# ArbPwrBoost_P3.net
KiCad netlist of a schematic drawn in Altium Designer
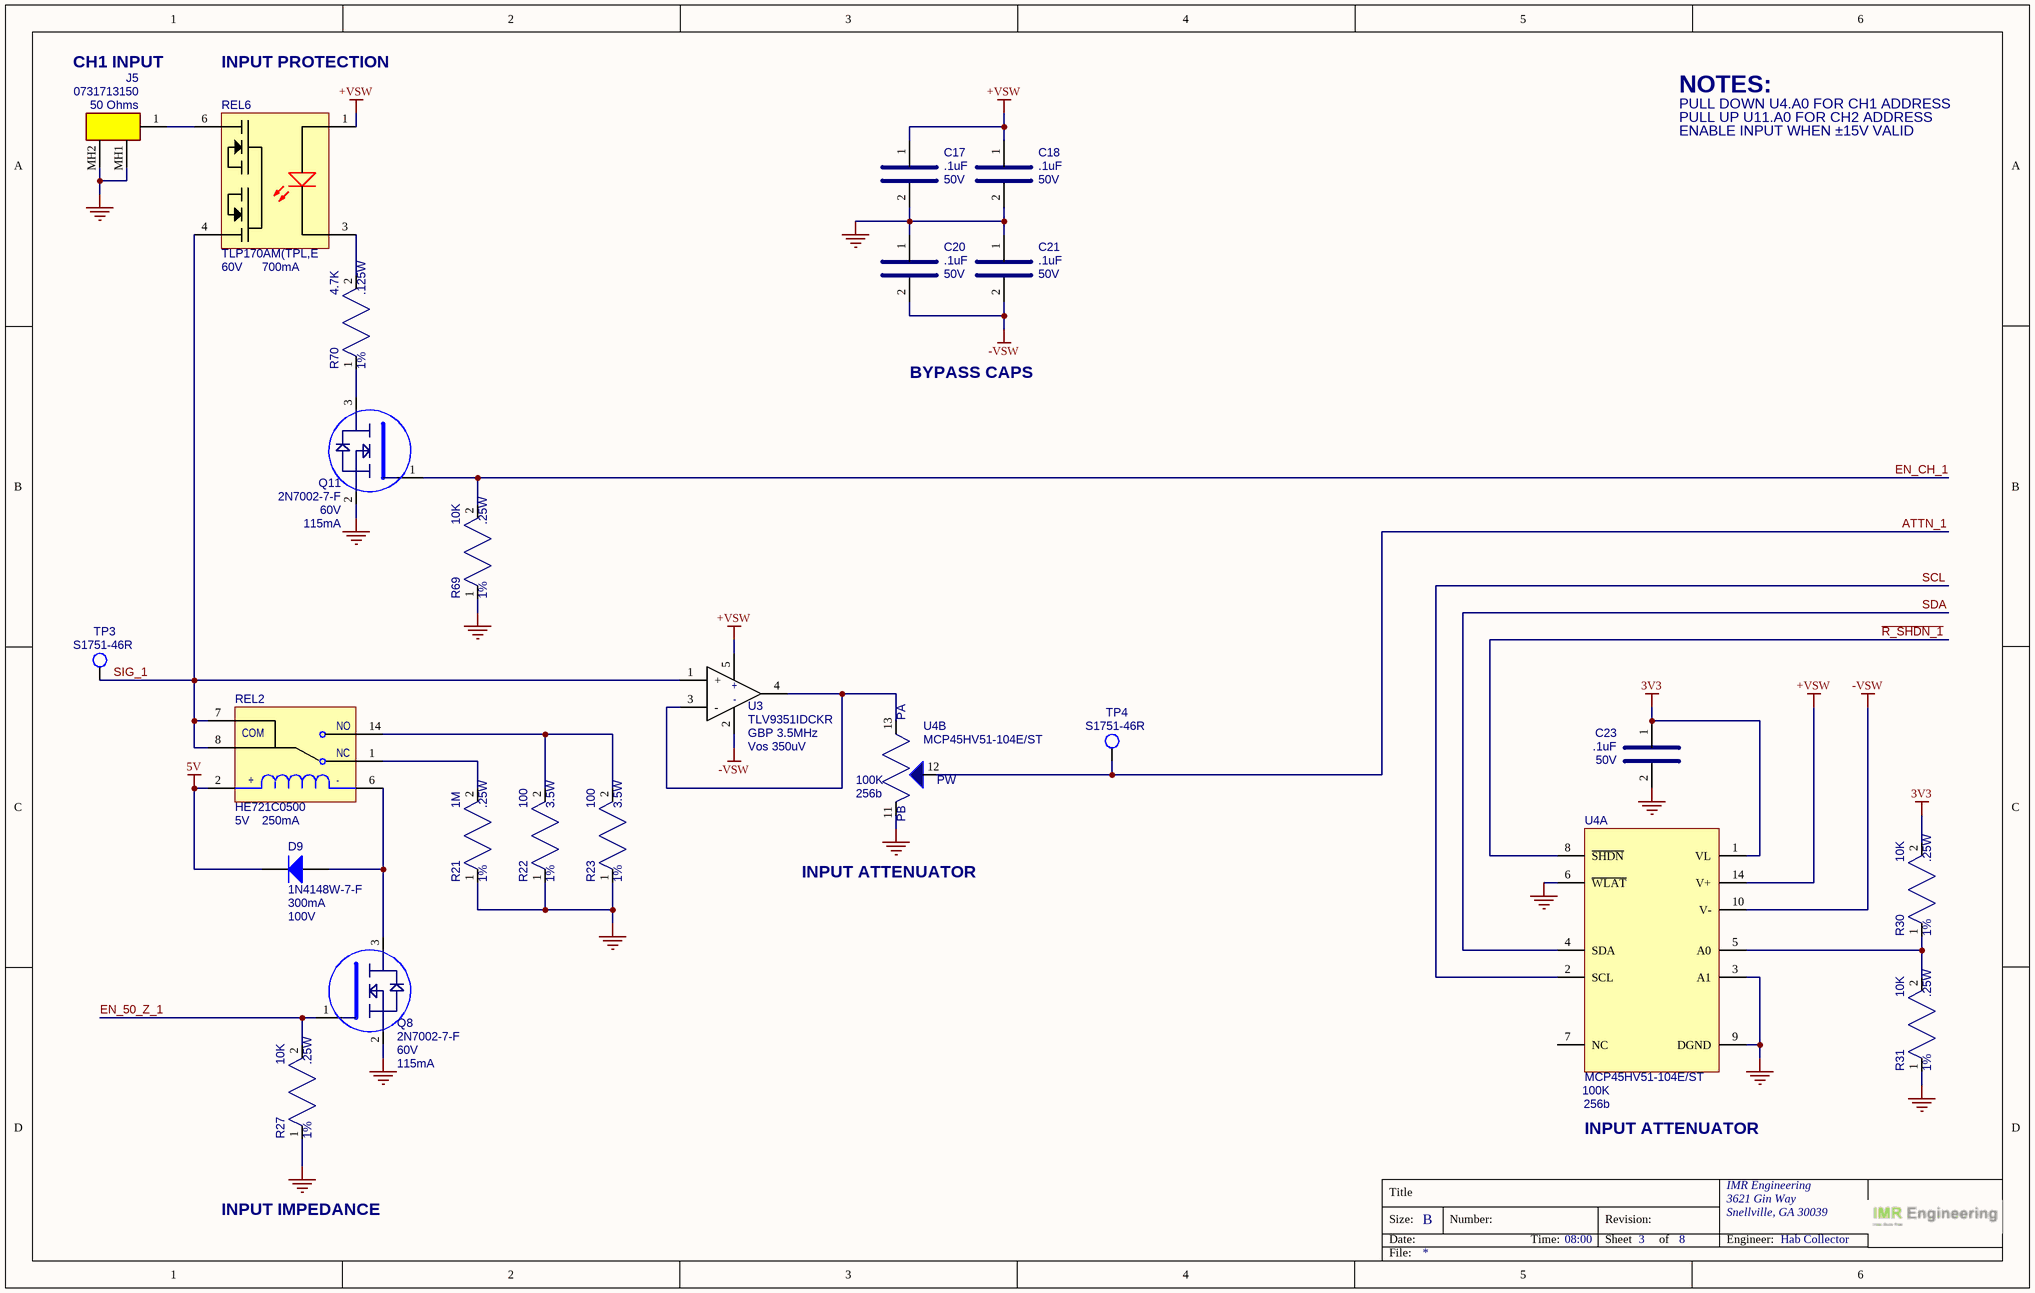
[diagram p0: ArbPwrBoost_P3.SchDoc]

(export (version "E")
  (design (tool "Eeschema 10.0.6"))
  (components
    (comp (ref "C17")
      (value ".1uF")
      (footprint "CAP_0805")
      (description "CAP CER 0.1UF 50V X7R 0805")
      (fields
        (field (name "MFG") "KYOCERA AVX")
        (field (name "VOLTAGE") "50V")
        (field (name "Comment") "KGM21NR71H104KT")
      )
      (libsource (lib "IMR_LIB_SCH_R2") (part "CAP_SMD_0.1UF_50V_0805"))
    )
    (comp (ref "C18")
      (value ".1uF")
      (footprint "CAP_0805")
      (description "CAP CER 0.1UF 50V X7R 0805")
      (fields
        (field (name "MFG") "KYOCERA AVX")
        (field (name "VOLTAGE") "50V")
        (field (name "Comment") "KGM21NR71H104KT")
      )
      (libsource (lib "IMR_LIB_SCH_R2") (part "CAP_SMD_0.1UF_50V_0805"))
    )
    (comp (ref "C20")
      (value ".1uF")
      (footprint "CAP_0805")
      (description "CAP CER 0.1UF 50V X7R 0805")
      (fields
        (field (name "MFG") "KYOCERA AVX")
        (field (name "VOLTAGE") "50V")
        (field (name "Comment") "KGM21NR71H104KT")
      )
      (libsource (lib "IMR_LIB_SCH_R2") (part "CAP_SMD_0.1UF_50V_0805"))
    )
    (comp (ref "C21")
      (value ".1uF")
      (footprint "CAP_0805")
      (description "CAP CER 0.1UF 50V X7R 0805")
      (fields
        (field (name "MFG") "KYOCERA AVX")
        (field (name "VOLTAGE") "50V")
        (field (name "Comment") "KGM21NR71H104KT")
      )
      (libsource (lib "IMR_LIB_SCH_R2") (part "CAP_SMD_0.1UF_50V_0805"))
    )
    (comp (ref "C23")
      (value ".1uF")
      (footprint "CAP_0805")
      (description "CAP CER 0.1UF 50V X7R 0805")
      (fields
        (field (name "MFG") "KYOCERA AVX")
        (field (name "VOLTAGE") "50V")
        (field (name "Comment") "KGM21NR71H104KT")
      )
      (libsource (lib "IMR_LIB_SCH_R2") (part "CAP_SMD_0.1UF_50V_0805"))
    )
    (comp (ref "D9")
      (value "100V")
      (footprint "SOD123")
      (description "RELAY REED SPDT 250MA 5V")
      (fields
        (field (name "MFG") "Diodes Inc")
        (field (name "MFG_PN") "1N4148W-7-F")
        (field (name "CURRENT") "300mA")
        (field (name "Comment") "1N4148W-7-F")
      )
      (libsource (lib "IMR_LIB_SCH_R2") (part "DIODE_1N4148W-7-F"))
    )
    (comp (ref "J5")
      (value "50 Ohms")
      (footprint "731713150")
      (description "CONN BNC RCPT R/A 50 OHM PCB")
      (fields
        (field (name "MFG") "Molex")
        (field (name "MFG_PN") "0731713150")
        (field (name "Comment") "0731713150")
      )
      (libsource (lib "IMR_LIB_SCH_R2") (part "CONN_MOLEX_0731713150"))
    )
    (comp (ref "Q8")
      (value "60V")
      (footprint "SOT-23")
      (description "MOSFET N-CH 60V 115MA SOT23-3")
      (fields
        (field (name "MFG") "Diodes Inc")
        (field (name "MFG_PN") "2N7002-7-F")
        (field (name "CURRENT") "115mA")
        (field (name "Comment") "2N7002-7-F")
      )
      (libsource (lib "") (part "MOSFET_NCH_2N7002-7-F_1"))
    )
    (comp (ref "Q11")
      (value "60V")
      (footprint "SOT-23")
      (description "MOSFET N-CH 60V 115MA SOT23-3")
      (fields
        (field (name "MFG") "Diodes Inc")
        (field (name "MFG_PN") "2N7002-7-F")
        (field (name "CURRENT") "115mA")
        (field (name "Comment") "2N7002-7-F")
      )
      (libsource (lib "IMR_LIB_SCH_R2") (part "MOSFET_NCH_2N7002-7-F"))
    )
    (comp (ref "R21")
      (value "1M")
      (footprint "RES_0805")
      (description "RES SMD 1K OHM 1% 1/4W 0805")
      (fields
        (field (name "MFG") "Yageo")
        (field (name "POWER") ".25W")
        (field (name "TOLERANCE") "1%")
        (field (name "Comment") "RC0805FR-7W1ML")
      )
      (libsource (lib "IMR_LIB_SCH_R2") (part "RES_SMD_1M_0805_1/4W_1%"))
    )
    (comp (ref "R22")
      (value "100")
      (footprint "RES_2512")
      (description "RES SMD 100 OHM 1% 3.5W 2512")
      (fields
        (field (name "MFG") "Ohmite")
        (field (name "POWER") "3.5W")
        (field (name "TOLERANCE") "1%")
        (field (name "Comment") "ALN2512F100RE-1")
      )
      (libsource (lib "IMR_LIB_SCH_R2") (part "RES_SMD_100_0805_3.5W_1%"))
    )
    (comp (ref "R23")
      (value "100")
      (footprint "RES_2512")
      (description "RES SMD 100 OHM 1% 3.5W 2512")
      (fields
        (field (name "MFG") "Ohmite")
        (field (name "POWER") "3.5W")
        (field (name "TOLERANCE") "1%")
        (field (name "Comment") "ALN2512F100RE-1")
      )
      (libsource (lib "IMR_LIB_SCH_R2") (part "RES_SMD_100_0805_3.5W_1%"))
    )
    (comp (ref "R27")
      (value "10K")
      (footprint "RES_0805")
      (description "RES SMD 10K OHM 1% 1/4W 0805")
      (fields
        (field (name "MFG") "Yageo")
        (field (name "POWER") ".25W")
        (field (name "TOLERANCE") "1%")
        (field (name "Comment") "RC0805FR-7W10KL")
      )
      (libsource (lib "IMR_LIB_SCH_R2") (part "RES_SMD_10K_0805_1/4W_1%"))
    )
    (comp (ref "R30")
      (value "10K")
      (footprint "RES_0805")
      (description "RES SMD 10K OHM 1% 1/4W 0805")
      (fields
        (field (name "MFG") "Yageo")
        (field (name "POWER") ".25W")
        (field (name "TOLERANCE") "1%")
        (field (name "Comment") "RC0805FR-7W10KL")
      )
      (libsource (lib "IMR_LIB_SCH_R2") (part "RES_SMD_10K_0805_1/4W_1%"))
    )
    (comp (ref "R31")
      (value "10K")
      (footprint "RES_0805")
      (description "RES SMD 10K OHM 1% 1/4W 0805")
      (fields
        (field (name "MFG") "Yageo")
        (field (name "POWER") ".25W")
        (field (name "TOLERANCE") "1%")
        (field (name "Comment") "RC0805FR-7W10KL")
      )
      (libsource (lib "IMR_LIB_SCH_R2") (part "RES_SMD_10K_0805_1/4W_1%"))
    )
    (comp (ref "R69")
      (value "10K")
      (footprint "RES_0805")
      (description "RES SMD 10K OHM 1% 1/4W 0805")
      (fields
        (field (name "MFG") "Yageo")
        (field (name "POWER") ".25W")
        (field (name "TOLERANCE") "1%")
        (field (name "Comment") "RC0805FR-7W10KL")
      )
      (libsource (lib "IMR_LIB_SCH_R2") (part "RES_SMD_10K_0805_1/4W_1%"))
    )
    (comp (ref "R70")
      (value "4.7K")
      (footprint "RES_0805")
      (description "RES SMD 4.7K OHM 1% 1/8W 0805")
      (fields
        (field (name "MFG") "Yageo")
        (field (name "POWER") ".125W")
        (field (name "TOLERANCE") "1%")
        (field (name "Comment") "RC0805FR-134K7L")
      )
      (libsource (lib "IMR_LIB_SCH_R2") (part "RES_SMD_4.7K_0805_1/8W_1%"))
    )
    (comp (ref "REL2")
      (value "5V")
      (footprint "HE700")
      (description "RELAY REED SPDT 250MA 5V")
      (fields
        (field (name "MFG") "Littlefuse")
        (field (name "MFG_PN") "HE721C0500")
        (field (name "CURRENT") "250mA")
        (field (name "Comment") "HE721C0500")
      )
      (libsource (lib "IMR_LIB_SCH_R2") (part "RELAY_HE721C0500"))
    )
    (comp (ref "REL6")
      (value "60V")
      (footprint "SOP-6")
      (description "SSR RELAY SPST-NO 700MA 0-60V")
      (fields
        (field (name "MFG") "Toshiba")
        (field (name "MFG_PN") "TLP170AM(TPL,E")
        (field (name "CURRENT") "700mA")
        (field (name "Comment") "TLP170AM(TPL,E")
      )
      (libsource (lib "IMR_LIB_SCH_R2") (part "RELAY_TLP170AM(TPL,E"))
    )
    (comp (ref "TP3")
      (value "S1751-46R")
      (footprint "HARWIN_S1751")
      (description "PCB TEST POINT CONNECT")
      (fields (field (name "MFG") "Harwin Inc") (field (name "MFG_PN") "S1751-46R"))
      (libsource (lib "IMR_LIB_SCH_R2") (part "CONN_TEST_POINT_S1751-46R"))
    )
    (comp (ref "TP4")
      (value "S1751-46R")
      (footprint "HARWIN_S1751")
      (description "PCB TEST POINT CONNECT")
      (fields (field (name "MFG") "Harwin Inc") (field (name "MFG_PN") "S1751-46R"))
      (libsource (lib "IMR_LIB_SCH_R2") (part "CONN_TEST_POINT_S1751-46R"))
    )
    (comp (ref "U3")
      (value "GBP 3.5MHz")
      (footprint "SOT-353")
      (description "IC OPAMP GP 3.5MHZ 350uV C70-5")
      (fields
        (field (name "MFG") "Texas Instruments")
        (field (name "MFG_PN") "TLV9351IDCKR")
        (field (name "VOS") "Vos 350uV")
        (field (name "Comment") "TLV9351IDCKR")
      )
      (libsource (lib "IMR_LIB_SCH_R2") (part "OPAMP_TLV9351IDCKR"))
    )
    (comp (ref "U4")
      (value "100K")
      (footprint "TSSOP-14")
      (description "IC DGT POT 100KOHM 256TP 14TSSOP")
      (fields
        (field (name "MFG") "Microchip")
        (field (name "MFG_PN") "MCP45HV51-104E/ST")
        (field (name "TAP") "256b")
        (field (name "Comment") "MCP45HV51-104E/ST")
      )
      (libsource (lib "IMR_LIB_SCH_R2") (part "IC_MCP45HV51-104E/ST"))
    )
  )
  (nets
    (net (code "1") (name "+VSW") (class "Default")
      (node (ref "C17") (pin "1") (pinfunction "1_1") (pintype "passive"))
      (node (ref "C18") (pin "1") (pinfunction "1_1") (pintype "passive"))
      (node (ref "REL6") (pin "1") (pinfunction "1_1") (pintype "passive"))
      (node (ref "U3") (pin "5") (pintype "passive"))
      (node (ref "U4") (pin "14") (pinfunction "V+_14") (pintype "passive"))
    )
    (net (code "2") (name "-VSW") (class "Default")
      (node (ref "C20") (pin "2") (pinfunction "2_2") (pintype "passive"))
      (node (ref "C21") (pin "2") (pinfunction "2_2") (pintype "passive"))
      (node (ref "U3") (pin "2") (pintype "passive"))
      (node (ref "U4") (pin "10") (pinfunction "V-_10") (pintype "passive"))
    )
    (net (code "3") (name "/ATTN_1") (class "Default")
      (node (ref "TP4") (pin "1") (pintype "passive"))
      (node (ref "U4") (pin "12") (pinfunction "PW0_12") (pintype "passive"))
    )
    (net (code "4") (name "/EN_50_Z_1") (class "Default")
      (node (ref "Q8") (pin "1") (pinfunction "B_1") (pintype "passive"))
      (node (ref "R27") (pin "2") (pinfunction "2_2") (pintype "passive"))
    )
    (net (code "5") (name "/EN_CH_1") (class "Default")
      (node (ref "Q11") (pin "1") (pinfunction "B_1") (pintype "passive"))
      (node (ref "R69") (pin "2") (pinfunction "2_2") (pintype "passive"))
    )
    (net (code "6") (name "/SCL") (class "Default")
      (node (ref "U4") (pin "2") (pinfunction "SCL_2") (pintype "passive"))
    )
    (net (code "7") (name "/SDA") (class "Default")
      (node (ref "U4") (pin "4") (pinfunction "SDA_4") (pintype "passive"))
    )
    (net (code "8") (name "/SIG_1") (class "Default")
      (node (ref "REL2") (pin "7") (pinfunction "COM_7") (pintype "passive"))
      (node (ref "REL2") (pin "8") (pinfunction "COM_8") (pintype "passive"))
      (node (ref "REL6") (pin "4") (pinfunction "4_4") (pintype "passive"))
      (node (ref "TP3") (pin "1") (pintype "passive"))
      (node (ref "U3") (pin "1") (pinfunction "+_1") (pintype "passive"))
    )
    (net (code "9") (name "/~{R_SHDN_1}") (class "Default")
      (node (ref "U4") (pin "8") (pinfunction "~{SHDN}_8") (pintype "passive"))
    )
    (net (code "10") (name "3V3") (class "Default")
      (node (ref "C23") (pin "1") (pinfunction "1_1") (pintype "passive"))
      (node (ref "R30") (pin "2") (pinfunction "2_2") (pintype "passive"))
      (node (ref "U4") (pin "1") (pinfunction "VL_1") (pintype "passive"))
    )
    (net (code "11") (name "5V") (class "Default")
      (node (ref "D9") (pin "2") (pinfunction "K_2") (pintype "passive"))
      (node (ref "REL2") (pin "2") (pintype "passive"))
    )
    (net (code "12") (name "GND") (class "Default")
      (node (ref "C17") (pin "2") (pinfunction "2_2") (pintype "passive"))
      (node (ref "C18") (pin "2") (pinfunction "2_2") (pintype "passive"))
      (node (ref "C20") (pin "1") (pinfunction "1_1") (pintype "passive"))
      (node (ref "C21") (pin "1") (pinfunction "1_1") (pintype "passive"))
      (node (ref "C23") (pin "2") (pinfunction "2_2") (pintype "passive"))
      (node (ref "J5") (pin "MH1") (pintype "passive"))
      (node (ref "J5") (pin "MH2") (pintype "passive"))
      (node (ref "Q11") (pin "2") (pinfunction "E_2") (pintype "passive"))
      (node (ref "Q8") (pin "2") (pinfunction "E_2") (pintype "passive"))
      (node (ref "R21") (pin "1") (pinfunction "1_1") (pintype "passive"))
      (node (ref "R22") (pin "1") (pinfunction "1_1") (pintype "passive"))
      (node (ref "R23") (pin "1") (pinfunction "1_1") (pintype "passive"))
      (node (ref "R27") (pin "1") (pinfunction "1_1") (pintype "passive"))
      (node (ref "R31") (pin "1") (pinfunction "1_1") (pintype "passive"))
      (node (ref "R69") (pin "1") (pinfunction "1_1") (pintype "passive"))
      (node (ref "U4") (pin "11") (pinfunction "PB0_11") (pintype "passive"))
      (node (ref "U4") (pin "3") (pinfunction "A1_3") (pintype "passive"))
      (node (ref "U4") (pin "6") (pinfunction "~{WLAT}_6") (pintype "passive"))
      (node (ref "U4") (pin "9") (pinfunction "DGND_9") (pintype "passive"))
    )
    (net (code "13") (name "Net-(D9-A)") (class "Default")
      (node (ref "D9") (pin "1") (pinfunction "A_1") (pintype "passive"))
      (node (ref "Q8") (pin "3") (pinfunction "C_3") (pintype "passive"))
      (node (ref "REL2") (pin "6") (pintype "passive"))
    )
    (net (code "14") (name "Net-(J5-Pad1)") (class "Default")
      (node (ref "J5") (pin "1") (pintype "passive"))
      (node (ref "REL6") (pin "6") (pinfunction "6_6") (pintype "passive"))
    )
    (net (code "15") (name "Net-(Q11-C)") (class "Default")
      (node (ref "Q11") (pin "3") (pinfunction "C_3") (pintype "passive"))
      (node (ref "R70") (pin "1") (pinfunction "1_1") (pintype "passive"))
    )
    (net (code "16") (name "Net-(R70-Pad2)") (class "Default")
      (node (ref "R70") (pin "2") (pinfunction "2_2") (pintype "passive"))
      (node (ref "REL6") (pin "3") (pinfunction "3_3") (pintype "passive"))
    )
    (net (code "17") (name "Net-(REL2-NC)") (class "Default")
      (node (ref "R21") (pin "2") (pinfunction "2_2") (pintype "passive"))
      (node (ref "REL2") (pin "1") (pinfunction "NC_1") (pintype "passive"))
    )
    (net (code "18") (name "Net-(REL2-NO)") (class "Default")
      (node (ref "R22") (pin "2") (pinfunction "2_2") (pintype "passive"))
      (node (ref "R23") (pin "2") (pinfunction "2_2") (pintype "passive"))
      (node (ref "REL2") (pin "14") (pinfunction "NO_14") (pintype "passive"))
    )
    (net (code "19") (name "Net-(U3--)") (class "Default")
      (node (ref "U3") (pin "3") (pinfunction "-_3") (pintype "passive"))
      (node (ref "U3") (pin "4") (pintype "passive"))
      (node (ref "U4") (pin "13") (pinfunction "PA_13") (pintype "passive"))
    )
    (net (code "20") (name "Net-(U4A-A0)") (class "Default")
      (node (ref "R30") (pin "1") (pinfunction "1_1") (pintype "passive"))
      (node (ref "R31") (pin "2") (pinfunction "2_2") (pintype "passive"))
      (node (ref "U4") (pin "5") (pinfunction "A0_5") (pintype "passive"))
    )
    (net (code "21") (name "unconnected-(U4A-NC-Pad7)") (class "Default")
      (node (ref "U4") (pin "7") (pinfunction "NC_7") (pintype "passive"))
    )
  )
)
